# 4_inverter.net
KiCad netlist of a schematic drawn in Altium Designer
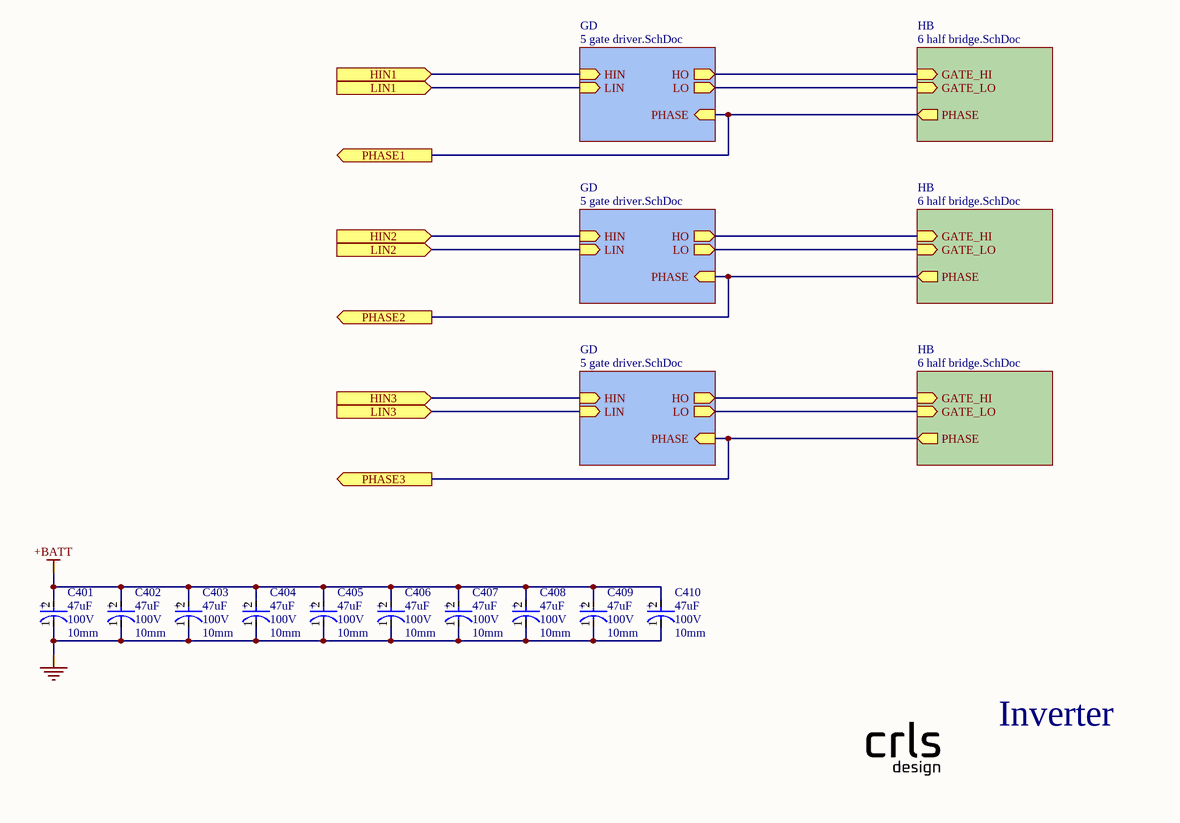
[diagram p0: 4 inverter.SchDoc]

(export (version "E")
  (design (tool "Eeschema 10.0.6"))
  (components
    (comp (ref "C401")
      (value "UUX2A470MNL1GS")
      (footprint "FP-UUX2A470MNL1GS-MFG")
      (description "CAP ALUM 47UF 20% 100V SMD")
      (fields
        (field (name "VOLTAGE") "100V")
        (field (name "TOLERANCE") "20%")
        (field (name "VOLTAGE RATING") "100V")
        (field (name "LENGTH") "10mm")
        (field (name "CAPACITANCE") "47uF")
      )
      (libsource (lib "Altium Content Vault") (part "cf48714ba7e38822c1575c7ec0b6d1f"))
    )
    (comp (ref "C402")
      (value "UUX2A470MNL1GS")
      (footprint "FP-UUX2A470MNL1GS-MFG")
      (description "CAP ALUM 47UF 20% 100V SMD")
      (fields
        (field (name "VOLTAGE") "100V")
        (field (name "TOLERANCE") "20%")
        (field (name "VOLTAGE RATING") "100V")
        (field (name "LENGTH") "10mm")
        (field (name "CAPACITANCE") "47uF")
      )
      (libsource (lib "Altium Content Vault") (part "cf48714ba7e38822c1575c7ec0b6d1f"))
    )
    (comp (ref "C403")
      (value "UUX2A470MNL1GS")
      (footprint "FP-UUX2A470MNL1GS-MFG")
      (description "CAP ALUM 47UF 20% 100V SMD")
      (fields
        (field (name "VOLTAGE") "100V")
        (field (name "TOLERANCE") "20%")
        (field (name "VOLTAGE RATING") "100V")
        (field (name "LENGTH") "10mm")
        (field (name "CAPACITANCE") "47uF")
      )
      (libsource (lib "Altium Content Vault") (part "cf48714ba7e38822c1575c7ec0b6d1f"))
    )
    (comp (ref "C404")
      (value "UUX2A470MNL1GS")
      (footprint "FP-UUX2A470MNL1GS-MFG")
      (description "CAP ALUM 47UF 20% 100V SMD")
      (fields
        (field (name "VOLTAGE") "100V")
        (field (name "TOLERANCE") "20%")
        (field (name "VOLTAGE RATING") "100V")
        (field (name "LENGTH") "10mm")
        (field (name "CAPACITANCE") "47uF")
      )
      (libsource (lib "Altium Content Vault") (part "cf48714ba7e38822c1575c7ec0b6d1f"))
    )
    (comp (ref "C405")
      (value "UUX2A470MNL1GS")
      (footprint "FP-UUX2A470MNL1GS-MFG")
      (description "CAP ALUM 47UF 20% 100V SMD")
      (fields
        (field (name "VOLTAGE") "100V")
        (field (name "TOLERANCE") "20%")
        (field (name "VOLTAGE RATING") "100V")
        (field (name "LENGTH") "10mm")
        (field (name "CAPACITANCE") "47uF")
      )
      (libsource (lib "Altium Content Vault") (part "cf48714ba7e38822c1575c7ec0b6d1f"))
    )
    (comp (ref "C406")
      (value "UUX2A470MNL1GS")
      (footprint "FP-UUX2A470MNL1GS-MFG")
      (description "CAP ALUM 47UF 20% 100V SMD")
      (fields
        (field (name "VOLTAGE") "100V")
        (field (name "TOLERANCE") "20%")
        (field (name "VOLTAGE RATING") "100V")
        (field (name "LENGTH") "10mm")
        (field (name "CAPACITANCE") "47uF")
      )
      (libsource (lib "Altium Content Vault") (part "cf48714ba7e38822c1575c7ec0b6d1f"))
    )
    (comp (ref "C407")
      (value "UUX2A470MNL1GS")
      (footprint "FP-UUX2A470MNL1GS-MFG")
      (description "CAP ALUM 47UF 20% 100V SMD")
      (fields
        (field (name "VOLTAGE") "100V")
        (field (name "TOLERANCE") "20%")
        (field (name "VOLTAGE RATING") "100V")
        (field (name "LENGTH") "10mm")
        (field (name "CAPACITANCE") "47uF")
      )
      (libsource (lib "Altium Content Vault") (part "cf48714ba7e38822c1575c7ec0b6d1f"))
    )
    (comp (ref "C408")
      (value "UUX2A470MNL1GS")
      (footprint "FP-UUX2A470MNL1GS-MFG")
      (description "CAP ALUM 47UF 20% 100V SMD")
      (fields
        (field (name "VOLTAGE") "100V")
        (field (name "TOLERANCE") "20%")
        (field (name "VOLTAGE RATING") "100V")
        (field (name "LENGTH") "10mm")
        (field (name "CAPACITANCE") "47uF")
      )
      (libsource (lib "Altium Content Vault") (part "cf48714ba7e38822c1575c7ec0b6d1f"))
    )
    (comp (ref "C409")
      (value "UUX2A470MNL1GS")
      (footprint "FP-UUX2A470MNL1GS-MFG")
      (description "CAP ALUM 47UF 20% 100V SMD")
      (fields
        (field (name "VOLTAGE") "100V")
        (field (name "TOLERANCE") "20%")
        (field (name "VOLTAGE RATING") "100V")
        (field (name "LENGTH") "10mm")
        (field (name "CAPACITANCE") "47uF")
      )
      (libsource (lib "Altium Content Vault") (part "cf48714ba7e38822c1575c7ec0b6d1f"))
    )
    (comp (ref "C410")
      (value "UUX2A470MNL1GS")
      (footprint "FP-UUX2A470MNL1GS-MFG")
      (description "CAP ALUM 47UF 20% 100V SMD")
      (fields
        (field (name "VOLTAGE") "100V")
        (field (name "TOLERANCE") "20%")
        (field (name "VOLTAGE RATING") "100V")
        (field (name "LENGTH") "10mm")
        (field (name "CAPACITANCE") "47uF")
      )
      (libsource (lib "Altium Content Vault") (part "cf48714ba7e38822c1575c7ec0b6d1f"))
    )
  )
  (nets
    (net (code "1") (name "+BATT") (class "Default")
      (node (ref "C401") (pin "2") (pinfunction "A_2") (pintype "passive"))
      (node (ref "C402") (pin "2") (pinfunction "A_2") (pintype "passive"))
      (node (ref "C403") (pin "2") (pinfunction "A_2") (pintype "passive"))
      (node (ref "C404") (pin "2") (pinfunction "A_2") (pintype "passive"))
      (node (ref "C405") (pin "2") (pinfunction "A_2") (pintype "passive"))
      (node (ref "C406") (pin "2") (pinfunction "A_2") (pintype "passive"))
      (node (ref "C407") (pin "2") (pinfunction "A_2") (pintype "passive"))
      (node (ref "C408") (pin "2") (pinfunction "A_2") (pintype "passive"))
      (node (ref "C409") (pin "2") (pinfunction "A_2") (pintype "passive"))
      (node (ref "C410") (pin "2") (pinfunction "A_2") (pintype "passive"))
    )
    (net (code "17") (name "GND") (class "Default")
      (node (ref "C401") (pin "1") (pinfunction "C_1") (pintype "passive"))
      (node (ref "C402") (pin "1") (pinfunction "C_1") (pintype "passive"))
      (node (ref "C403") (pin "1") (pinfunction "C_1") (pintype "passive"))
      (node (ref "C404") (pin "1") (pinfunction "C_1") (pintype "passive"))
      (node (ref "C405") (pin "1") (pinfunction "C_1") (pintype "passive"))
      (node (ref "C406") (pin "1") (pinfunction "C_1") (pintype "passive"))
      (node (ref "C407") (pin "1") (pinfunction "C_1") (pintype "passive"))
      (node (ref "C408") (pin "1") (pinfunction "C_1") (pintype "passive"))
      (node (ref "C409") (pin "1") (pinfunction "C_1") (pintype "passive"))
      (node (ref "C410") (pin "1") (pinfunction "C_1") (pintype "passive"))
    )
  )
)
